# openSX70_ALADDIN_V395SEEED_20180208.net
KiCad netlist of a schematic drawn in EAGLE
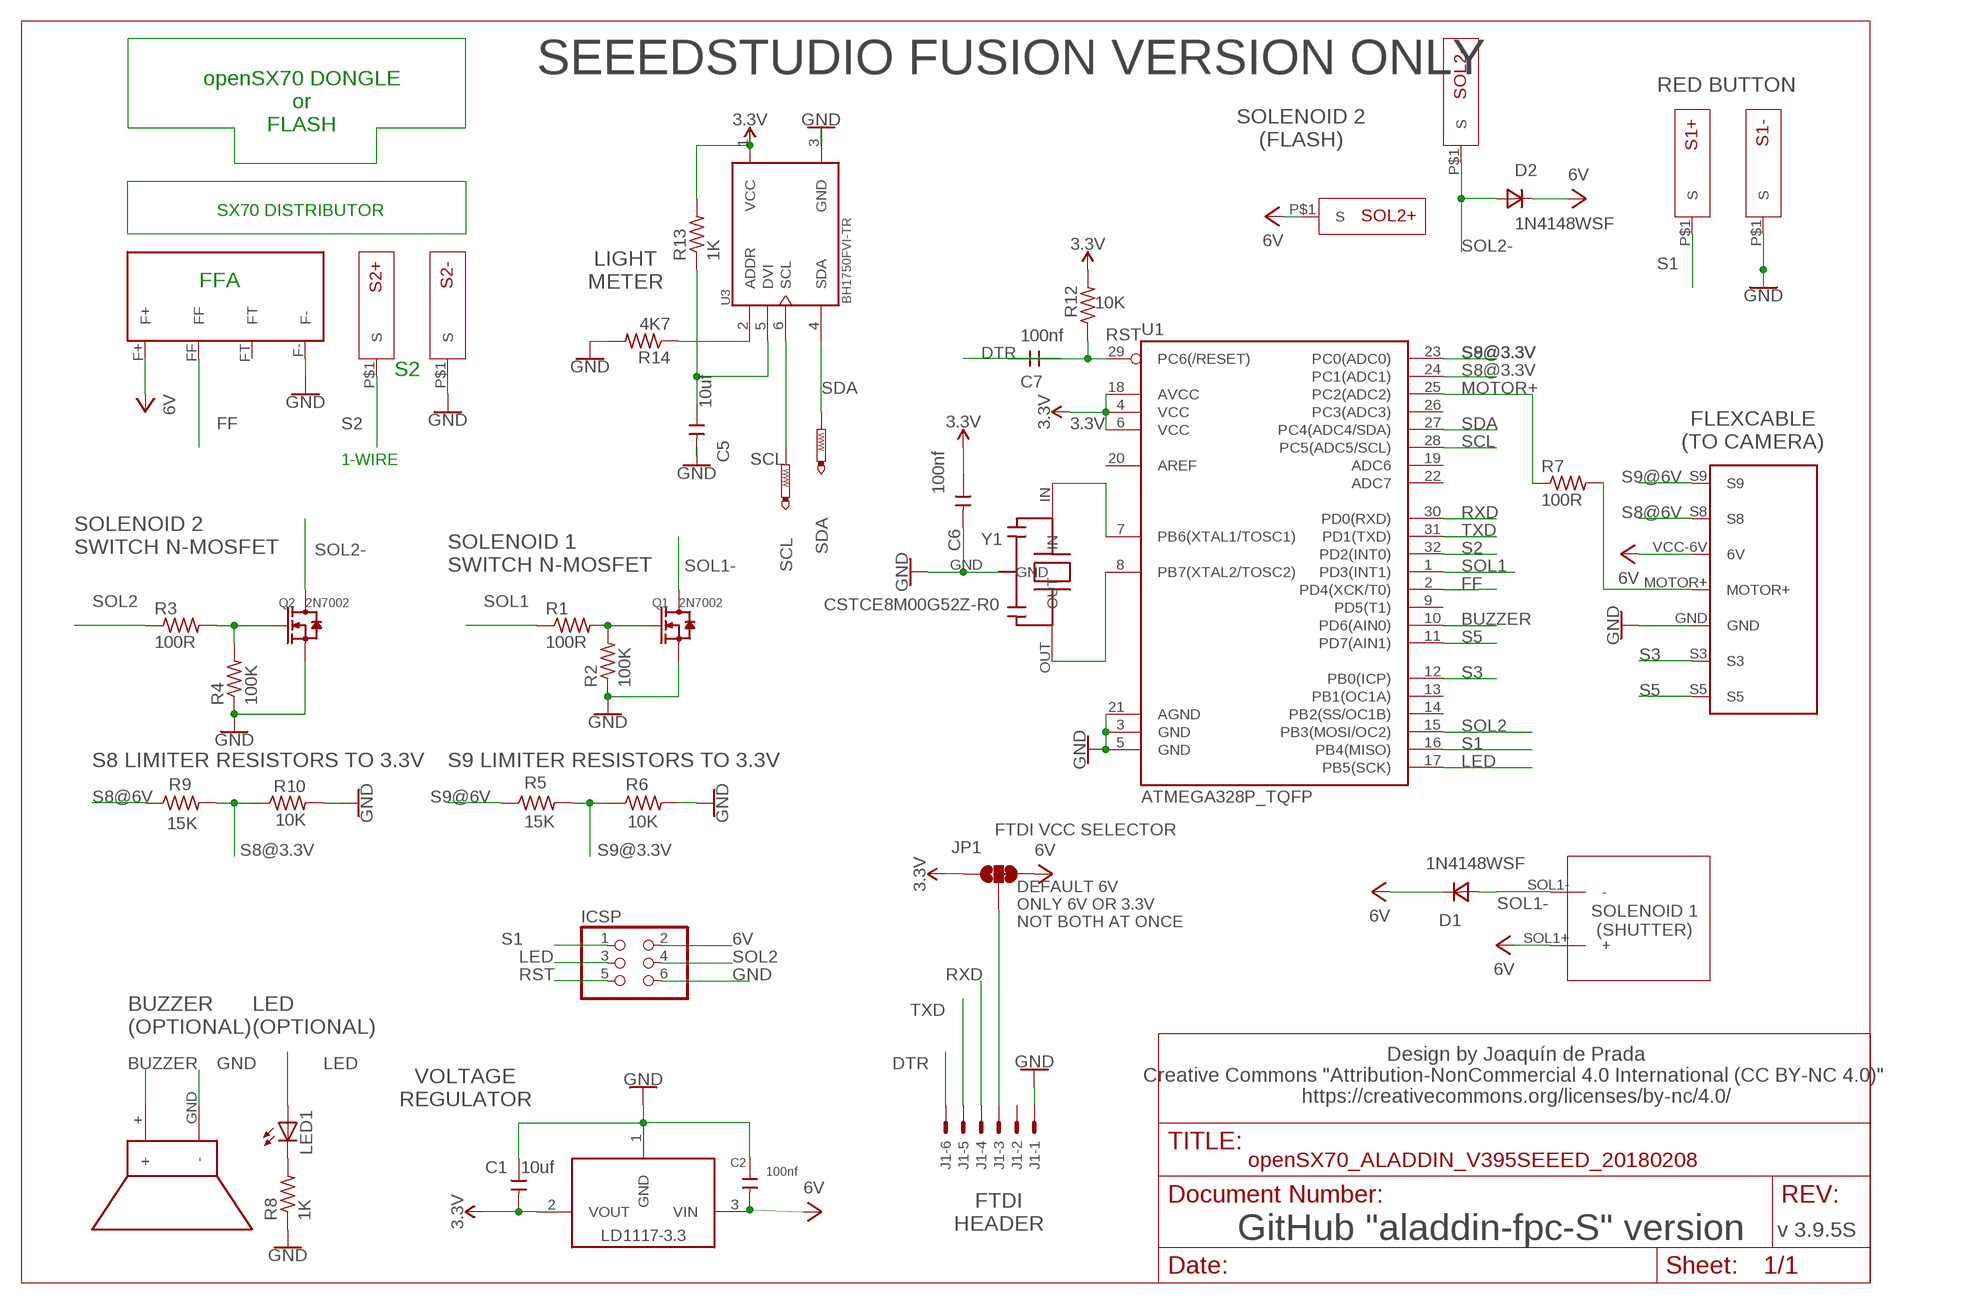
[diagram p0: schematic, sheet 1]

(export (version "E")
  (design (tool "Eeschema 10.0.6"))
  (components
    (comp (ref "C1")
      (value "10uf")
      (footprint "eagle-import:C0603")
      (fields (field (name "MPN") "CC0603KRX5R6BB106"))
      (libsource (lib "eagle-import") (part "CERAMIC-10UF-10V-10%-X5R(0603)"))
    )
    (comp (ref "C2")
      (value "100nf")
      (footprint "eagle-import:C0603")
      (fields (field (name "MPN") "CC0603KRX7R9BB104"))
      (libsource (lib "eagle-import") (part "CERAMIC-100NF-50V-10%-X7R(0603)"))
    )
    (comp (ref "C5")
      (value "10uf")
      (footprint "eagle-import:C0603")
      (fields (field (name "MPN") "CC0603KRX5R6BB106"))
      (libsource (lib "eagle-import") (part "CERAMIC-10UF-10V-10%-X5R(0603)"))
    )
    (comp (ref "C6")
      (value "100nf")
      (footprint "eagle-import:C0603")
      (fields (field (name "MPN") "CC0603KRX7R9BB104"))
      (libsource (lib "eagle-import") (part "CERAMIC-100NF-50V-10%-X7R(0603)"))
    )
    (comp (ref "C7")
      (value "100nf")
      (footprint "eagle-import:C0603")
      (fields (field (name "MPN") "CC0603KRX7R9BB104"))
      (libsource (lib "eagle-import") (part "CERAMIC-100NF-50V-10%-X7R(0603)"))
    )
    (comp (ref "D1")
      (value "1N4148WSF")
      (footprint "eagle-import:SOD323")
      (fields (field (name "MPN") "CDSOD323-T05C"))
      (libsource (lib "eagle-import") (part "DSOD323"))
    )
    (comp (ref "D2")
      (value "1N4148WSF")
      (footprint "eagle-import:SOD323")
      (fields (field (name "MPN") "CDSOD323-T05C"))
      (libsource (lib "eagle-import") (part "DSOD323"))
    )
    (comp (ref "ICSP")
      (value "PINHD-2X3")
      (footprint "eagle-import:2X03")
      (libsource (lib "eagle-import") (part "PINHD-2X3"))
    )
    (comp (ref "J1")
      (value "GND")
      (footprint "eagle-import:XF2L-0625-1")
      (fields (field (name "MF") "OMRON COMPONENTS USA") (field (name "MPN") "XF2L-0625-1"))
      (libsource (lib "eagle-import") (part "XF2-06?25-1L"))
    )
    (comp (ref "JP1")
      (value "FTDI VCC SELECTOR")
      (footprint "eagle-import:SMT-JUMPER_3_1-NC_TRACE_SILK")
      (libsource (lib "eagle-import") (part "JUMPER-SMT_3_1-NC_TRACE_SILK"))
    )
    (comp (ref "LD11172.5V")
      (value "LD1117 2.5V")
      (footprint "eagle-import:SOT223")
      (fields (field (name "MF") "Advanced Monolithic Systems") (field (name "MP") "AMS1117-5.0"))
      (libsource (lib "eagle-import") (part "LD1117-3.3"))
    )
    (comp (ref "LED1")
      (value "LEDCHIPLED_0805")
      (footprint "eagle-import:CHIPLED_0805")
      (libsource (lib "eagle-import") (part "LEDCHIPLED_0805"))
    )
    (comp (ref "Q1")
      (value "2N7002")
      (footprint "eagle-import:SOT-23")
      (fields (field (name "MPN") "2N7002,215"))
      (libsource (lib "eagle-import") (part "SMD-MOSFET-N-CH-60V-300MA-LOGIC-LEVEL-FET-2N7002(SOT-23)"))
    )
    (comp (ref "Q2")
      (value "2N7002")
      (footprint "eagle-import:SOT-23")
      (fields (field (name "MPN") "2N7002,215"))
      (libsource (lib "eagle-import") (part "SMD-MOSFET-N-CH-60V-300MA-LOGIC-LEVEL-FET-2N7002(SOT-23)"))
    )
    (comp (ref "R1")
      (value "100R")
      (footprint "eagle-import:R0603")
      (libsource (lib "eagle-import") (part "R-US_R0603"))
    )
    (comp (ref "R2")
      (value "100K")
      (footprint "eagle-import:R0603")
      (libsource (lib "eagle-import") (part "R-US_R0603"))
    )
    (comp (ref "R3")
      (value "100R")
      (footprint "eagle-import:R0603")
      (libsource (lib "eagle-import") (part "R-US_R0603"))
    )
    (comp (ref "R4")
      (value "100K")
      (footprint "eagle-import:R0603")
      (libsource (lib "eagle-import") (part "R-US_R0603"))
    )
    (comp (ref "R5")
      (value "15K")
      (footprint "eagle-import:R0603")
      (libsource (lib "eagle-import") (part "R-US_R0603"))
    )
    (comp (ref "R6")
      (value "10K")
      (footprint "eagle-import:R0603")
      (libsource (lib "eagle-import") (part "R-US_R0603"))
    )
    (comp (ref "R7")
      (value "100R")
      (footprint "eagle-import:R0603")
      (libsource (lib "eagle-import") (part "R-US_R0603"))
    )
    (comp (ref "R8")
      (value "1K")
      (footprint "eagle-import:R0603")
      (libsource (lib "eagle-import") (part "R-US_R0603"))
    )
    (comp (ref "R9")
      (value "15K")
      (footprint "eagle-import:R0603")
      (libsource (lib "eagle-import") (part "R-US_R0603"))
    )
    (comp (ref "R10")
      (value "10K")
      (footprint "eagle-import:R0603")
      (libsource (lib "eagle-import") (part "R-US_R0603"))
    )
    (comp (ref "R12")
      (value "10K")
      (footprint "eagle-import:R0603")
      (libsource (lib "eagle-import") (part "R-US_R0603"))
    )
    (comp (ref "R13")
      (value "1K")
      (footprint "eagle-import:R0603")
      (libsource (lib "eagle-import") (part "R-US_R0603"))
    )
    (comp (ref "R14")
      (value "4K7")
      (footprint "eagle-import:R0603")
      (libsource (lib "eagle-import") (part "R-US_R0603"))
    )
    (comp (ref "S1+")
      (value "SX70-S-PAD-NEW")
      (footprint "eagle-import:SX70-S-PAD2")
      (libsource (lib "eagle-import") (part "SX70-S-PAD-NEW"))
    )
    (comp (ref "S1-")
      (value "SX70-S-PAD-NEW")
      (footprint "eagle-import:SX70-S-PAD2")
      (libsource (lib "eagle-import") (part "SX70-S-PAD-NEW"))
    )
    (comp (ref "S2+")
      (value "SX70-S-PAD-NEW")
      (footprint "eagle-import:SX70-S-PAD2")
      (libsource (lib "eagle-import") (part "SX70-S-PAD-NEW"))
    )
    (comp (ref "S2-")
      (value "SX70-S-PAD-NEW")
      (footprint "eagle-import:SX70-S-PAD2")
      (libsource (lib "eagle-import") (part "SX70-S-PAD-NEW"))
    )
    (comp (ref "SCL")
      (value "PTR1TP08R")
      (footprint "eagle-import:TP08R")
      (libsource (lib "eagle-import") (part "PTR1TP08R"))
    )
    (comp (ref "SDA")
      (value "PTR1TP08R")
      (footprint "eagle-import:TP08R")
      (libsource (lib "eagle-import") (part "PTR1TP08R"))
    )
    (comp (ref "SOL1")
      (value "SX70-SOLENOID1-2PADS")
      (footprint "eagle-import:SX70-SOLENOID1-2")
      (libsource (lib "eagle-import") (part "SX70-SOLENOID1-2PADS"))
    )
    (comp (ref "SOL2+")
      (value "SX70-S-PAD-NEW")
      (footprint "eagle-import:SX70-S-PAD2")
      (libsource (lib "eagle-import") (part "SX70-S-PAD-NEW"))
    )
    (comp (ref "SOL2-")
      (value "SX70-S-PAD-NEW")
      (footprint "eagle-import:SX70-S-PAD2")
      (libsource (lib "eagle-import") (part "SX70-S-PAD-NEW"))
    )
    (comp (ref "U$1")
      (value "SX70-7-PAD")
      (footprint "eagle-import:SX70-7-PAD")
      (libsource (lib "eagle-import") (part "SX70-7-PAD"))
    )
    (comp (ref "U$2")
      (value "FFA")
      (footprint "eagle-import:FFA-PAD-PACKAGE")
      (libsource (lib "eagle-import") (part "SX70-FFA-PAD"))
    )
    (comp (ref "U$3")
      (value "CSET8-5G_V2")
      (footprint "eagle-import:CSET8-5G_PACKAGE")
      (libsource (lib "eagle-import") (part "CSET8-5G_V2"))
    )
    (comp (ref "U1")
      (value "ATMEGA328P_TQFP")
      (footprint "eagle-import:TQFP32-08")
      (libsource (lib "eagle-import") (part "ATMEGA328P_TQFP"))
    )
    (comp (ref "U3")
      (value "BH1750FVI-TR")
      (footprint "eagle-import:SOTFL50P300X75-6N")
      (fields (field (name "MF") "Rohm"))
      (libsource (lib "eagle-import") (part "BH1750FVI-TR"))
    )
    (comp (ref "Y1")
      (value "CSTCE8M00G52Z-R0")
      (footprint "eagle-import:CFP95P160X100-3N")
      (fields (field (name "MF") "Murata") (field (name "MP") "CSTCE16M0V53-R0"))
      (libsource (lib "eagle-import") (part "CSTCE16M0V53-R0"))
    )
  )
  (nets
    (net (code "1") (name "/BUZZER") (class "Default")
      (node (ref "U$3") (pin "+") (pinfunction "+_+") (pintype "bidirectional"))
      (node (ref "U1") (pin "10") (pinfunction "PD6(AIN0)_10") (pintype "bidirectional"))
    )
    (net (code "2") (name "/DTR") (class "Default")
      (node (ref "C7") (pin "1") (pinfunction "1_1") (pintype "passive"))
      (node (ref "J1") (pin "6") (pinfunction "MS_6") (pintype "passive"))
    )
    (net (code "3") (name "/FF") (class "Default")
      (node (ref "U$2") (pin "FF") (pinfunction "FF_FF") (pintype "bidirectional"))
      (node (ref "U1") (pin "2") (pinfunction "PD4(XCK/T0)_2") (pintype "bidirectional"))
    )
    (net (code "4") (name "/LED") (class "Default")
      (node (ref "ICSP") (pin "3") (pinfunction "3_3") (pintype "passive"))
      (node (ref "LED1") (pin "A") (pinfunction "A_A") (pintype "passive"))
      (node (ref "U1") (pin "17") (pinfunction "PB5(SCK)_17") (pintype "bidirectional"))
    )
    (net (code "5") (name "/MOTOR+") (class "Default")
      (node (ref "R7") (pin "1") (pinfunction "1_1") (pintype "passive"))
      (node (ref "U1") (pin "25") (pinfunction "PC2(ADC2)_25") (pintype "bidirectional"))
    )
    (net (code "6") (name "/RST") (class "Default")
      (node (ref "C7") (pin "2") (pinfunction "2_2") (pintype "passive"))
      (node (ref "ICSP") (pin "5") (pinfunction "5_5") (pintype "passive"))
      (node (ref "R12") (pin "1") (pinfunction "1_1") (pintype "passive"))
      (node (ref "U1") (pin "29") (pinfunction "PC6(/RESET)_29") (pintype "bidirectional"))
    )
    (net (code "7") (name "/RXD") (class "Default")
      (node (ref "J1") (pin "4") (pinfunction "MS_4") (pintype "passive"))
      (node (ref "U1") (pin "30") (pinfunction "PD0(RXD)_30") (pintype "bidirectional"))
    )
    (net (code "8") (name "/S1") (class "Default")
      (node (ref "ICSP") (pin "1") (pinfunction "1_1") (pintype "passive"))
      (node (ref "S1+") (pin "P$1") (pinfunction "S_P$1") (pintype "bidirectional"))
      (node (ref "U1") (pin "16") (pinfunction "PB4(MISO)_16") (pintype "bidirectional"))
    )
    (net (code "9") (name "/S2") (class "Default")
      (node (ref "S2+") (pin "P$1") (pinfunction "S_P$1") (pintype "bidirectional"))
      (node (ref "U1") (pin "32") (pinfunction "PD2(INT0)_32") (pintype "bidirectional"))
    )
    (net (code "10") (name "/S3") (class "Default")
      (node (ref "U$1") (pin "S3") (pinfunction "S3_S3") (pintype "bidirectional"))
      (node (ref "U1") (pin "12") (pinfunction "PB0(ICP)_12") (pintype "bidirectional"))
    )
    (net (code "11") (name "/S5") (class "Default")
      (node (ref "U$1") (pin "S5") (pinfunction "S5_S5") (pintype "bidirectional"))
      (node (ref "U1") (pin "11") (pinfunction "PD7(AIN1)_11") (pintype "bidirectional"))
    )
    (net (code "12") (name "/S8@3.3V") (class "Default")
      (node (ref "R10") (pin "1") (pinfunction "1_1") (pintype "passive"))
      (node (ref "R9") (pin "2") (pinfunction "2_2") (pintype "passive"))
      (node (ref "U1") (pin "24") (pinfunction "PC1(ADC1)_24") (pintype "bidirectional"))
    )
    (net (code "13") (name "/S8@6V") (class "Default")
      (node (ref "R9") (pin "1") (pinfunction "1_1") (pintype "passive"))
      (node (ref "U$1") (pin "S8") (pinfunction "S8_S8") (pintype "bidirectional"))
    )
    (net (code "14") (name "/S9@3.3V") (class "Default")
      (node (ref "R5") (pin "2") (pinfunction "2_2") (pintype "passive"))
      (node (ref "R6") (pin "1") (pinfunction "1_1") (pintype "passive"))
      (node (ref "U1") (pin "23") (pinfunction "PC0(ADC0)_23") (pintype "bidirectional"))
    )
    (net (code "15") (name "/S9@6V") (class "Default")
      (node (ref "R5") (pin "1") (pinfunction "1_1") (pintype "passive"))
      (node (ref "U$1") (pin "S9") (pinfunction "S9_S9") (pintype "bidirectional"))
    )
    (net (code "16") (name "/SCL") (class "Default")
      (node (ref "SCL") (pin "TP") (pinfunction "TP_TP") (pintype "input"))
      (node (ref "U1") (pin "28") (pinfunction "PC5(ADC5/SCL)_28") (pintype "bidirectional"))
      (node (ref "U3") (pin "6") (pinfunction "SCL_6") (pintype "input"))
    )
    (net (code "17") (name "/SDA") (class "Default")
      (node (ref "SDA") (pin "TP") (pinfunction "TP_TP") (pintype "input"))
      (node (ref "U1") (pin "27") (pinfunction "PC4(ADC4/SDA)_27") (pintype "bidirectional"))
      (node (ref "U3") (pin "4") (pinfunction "SDA_4") (pintype "bidirectional"))
    )
    (net (code "18") (name "/SOL1") (class "Default")
      (node (ref "R1") (pin "1") (pinfunction "1_1") (pintype "passive"))
      (node (ref "U1") (pin "1") (pinfunction "PD3(INT1)_1") (pintype "bidirectional"))
    )
    (net (code "19") (name "/SOL1-") (class "Default")
      (node (ref "D1") (pin "2") (pinfunction "A_2") (pintype "passive"))
      (node (ref "Q1") (pin "3") (pinfunction "D_3") (pintype "passive"))
      (node (ref "SOL1") (pin "SOL1-") (pinfunction "-_SOL1-") (pintype "bidirectional"))
    )
    (net (code "20") (name "/SOL2") (class "Default")
      (node (ref "ICSP") (pin "4") (pinfunction "4_4") (pintype "passive"))
      (node (ref "R3") (pin "1") (pinfunction "1_1") (pintype "passive"))
      (node (ref "U1") (pin "15") (pinfunction "PB3(MOSI/OC2)_15") (pintype "bidirectional"))
    )
    (net (code "21") (name "/SOL2-") (class "Default")
      (node (ref "D2") (pin "2") (pinfunction "A_2") (pintype "passive"))
      (node (ref "Q2") (pin "3") (pinfunction "D_3") (pintype "passive"))
      (node (ref "SOL2-") (pin "P$1") (pinfunction "S_P$1") (pintype "bidirectional"))
    )
    (net (code "22") (name "/TXD") (class "Default")
      (node (ref "J1") (pin "5") (pinfunction "MS_5") (pintype "passive"))
      (node (ref "U1") (pin "31") (pinfunction "PD1(TXD)_31") (pintype "bidirectional"))
    )
    (net (code "23") (name "3.3V") (class "Default")
      (node (ref "C1") (pin "2") (pinfunction "2_2") (pintype "passive"))
      (node (ref "C6") (pin "1") (pinfunction "1_1") (pintype "passive"))
      (node (ref "JP1") (pin "1") (pinfunction "1_1") (pintype "passive"))
      (node (ref "LD11172.5V") (pin "2") (pinfunction "VOUT_2") (pintype "bidirectional"))
      (node (ref "R12") (pin "2") (pinfunction "2_2") (pintype "passive"))
      (node (ref "R13") (pin "2") (pinfunction "2_2") (pintype "passive"))
      (node (ref "U1") (pin "18") (pinfunction "AVCC_18") (pintype "bidirectional"))
      (node (ref "U1") (pin "4") (pinfunction "VCC_4") (pintype "bidirectional"))
      (node (ref "U1") (pin "6") (pinfunction "VCC_6") (pintype "bidirectional"))
      (node (ref "U3") (pin "1") (pinfunction "VCC_1") (pintype "power_in"))
    )
    (net (code "24") (name "6V") (class "Default")
      (node (ref "C2") (pin "2") (pinfunction "2_2") (pintype "passive"))
      (node (ref "D1") (pin "1") (pinfunction "C_1") (pintype "passive"))
      (node (ref "D2") (pin "1") (pinfunction "C_1") (pintype "passive"))
      (node (ref "ICSP") (pin "2") (pinfunction "2_2") (pintype "passive"))
      (node (ref "JP1") (pin "3") (pinfunction "3_3") (pintype "passive"))
      (node (ref "LD11172.5V") (pin "3") (pinfunction "VIN_3") (pintype "bidirectional"))
      (node (ref "SOL1") (pin "SOL1+") (pinfunction "+_SOL1+") (pintype "bidirectional"))
      (node (ref "SOL2+") (pin "P$1") (pinfunction "S_P$1") (pintype "bidirectional"))
      (node (ref "U$1") (pin "VCC-6V") (pinfunction "6V_VCC-6V") (pintype "bidirectional"))
      (node (ref "U$2") (pin "F+") (pinfunction "F+_F+") (pintype "bidirectional"))
    )
    (net (code "25") (name "GND") (class "Default")
      (node (ref "C1") (pin "1") (pinfunction "1_1") (pintype "passive"))
      (node (ref "C2") (pin "1") (pinfunction "1_1") (pintype "passive"))
      (node (ref "C5") (pin "2") (pinfunction "2_2") (pintype "passive"))
      (node (ref "C6") (pin "2") (pinfunction "2_2") (pintype "passive"))
      (node (ref "ICSP") (pin "6") (pinfunction "6_6") (pintype "passive"))
      (node (ref "J1") (pin "1") (pinfunction "MS_1") (pintype "passive"))
      (node (ref "LD11172.5V") (pin "1") (pinfunction "GND_1") (pintype "bidirectional"))
      (node (ref "Q1") (pin "2") (pinfunction "S_2") (pintype "passive"))
      (node (ref "Q2") (pin "2") (pinfunction "S_2") (pintype "passive"))
      (node (ref "R10") (pin "2") (pinfunction "2_2") (pintype "passive"))
      (node (ref "R14") (pin "2") (pinfunction "2_2") (pintype "passive"))
      (node (ref "R2") (pin "1") (pinfunction "1_1") (pintype "passive"))
      (node (ref "R4") (pin "1") (pinfunction "1_1") (pintype "passive"))
      (node (ref "R6") (pin "2") (pinfunction "2_2") (pintype "passive"))
      (node (ref "R8") (pin "1") (pinfunction "1_1") (pintype "passive"))
      (node (ref "S1-") (pin "P$1") (pinfunction "S_P$1") (pintype "bidirectional"))
      (node (ref "S2-") (pin "P$1") (pinfunction "S_P$1") (pintype "bidirectional"))
      (node (ref "U$1") (pin "GND") (pinfunction "GND_GND") (pintype "bidirectional"))
      (node (ref "U$2") (pin "F-") (pinfunction "F-_F-") (pintype "bidirectional"))
      (node (ref "U$3") (pin "GND") (pinfunction "-_GND") (pintype "bidirectional"))
      (node (ref "U1") (pin "21") (pinfunction "AGND_21") (pintype "bidirectional"))
      (node (ref "U1") (pin "3") (pinfunction "GND_3") (pintype "bidirectional"))
      (node (ref "U1") (pin "5") (pinfunction "GND_5") (pintype "bidirectional"))
      (node (ref "U3") (pin "3") (pinfunction "GND_3") (pintype "power_in"))
      (node (ref "Y1") (pin "GND") (pinfunction "GND_GND") (pintype "passive"))
    )
    (net (code "26") (name "Net-(J1C-MS)") (class "Default")
      (node (ref "J1") (pin "3") (pinfunction "MS_3") (pintype "passive"))
      (node (ref "JP1") (pin "2") (pinfunction "2_2") (pintype "passive"))
    )
    (net (code "27") (name "Net-(LED1-PadC)") (class "Default")
      (node (ref "LED1") (pin "C") (pinfunction "C_C") (pintype "passive"))
      (node (ref "R8") (pin "2") (pinfunction "2_2") (pintype "passive"))
    )
    (net (code "28") (name "Net-(Q1-G)") (class "Default")
      (node (ref "Q1") (pin "1") (pinfunction "G_1") (pintype "passive"))
      (node (ref "R1") (pin "2") (pinfunction "2_2") (pintype "passive"))
      (node (ref "R2") (pin "2") (pinfunction "2_2") (pintype "passive"))
    )
    (net (code "29") (name "Net-(Q2-G)") (class "Default")
      (node (ref "Q2") (pin "1") (pinfunction "G_1") (pintype "passive"))
      (node (ref "R3") (pin "2") (pinfunction "2_2") (pintype "passive"))
      (node (ref "R4") (pin "2") (pinfunction "2_2") (pintype "passive"))
    )
    (net (code "30") (name "Net-(R7-Pad2)") (class "Default")
      (node (ref "R7") (pin "2") (pinfunction "2_2") (pintype "passive"))
      (node (ref "U$1") (pin "MOTOR+") (pinfunction "MOTOR+_MOTOR+") (pintype "bidirectional"))
    )
    (net (code "31") (name "Net-(U1-PB6(XTAL1{slash}TOSC1))") (class "Default")
      (node (ref "U1") (pin "7") (pinfunction "PB6(XTAL1/TOSC1)_7") (pintype "bidirectional"))
      (node (ref "Y1") (pin "IN") (pinfunction "IN_IN") (pintype "input"))
    )
    (net (code "32") (name "Net-(U1-PB7(XTAL2{slash}TOSC2))") (class "Default")
      (node (ref "U1") (pin "8") (pinfunction "PB7(XTAL2/TOSC2)_8") (pintype "bidirectional"))
      (node (ref "Y1") (pin "OUT") (pinfunction "OUT_OUT") (pintype "output"))
    )
    (net (code "33") (name "Net-(U3-ADDR)") (class "Default")
      (node (ref "R14") (pin "1") (pinfunction "1_1") (pintype "passive"))
      (node (ref "U3") (pin "2") (pinfunction "ADDR_2") (pintype "input"))
    )
    (net (code "34") (name "Net-(U3-DVI)") (class "Default")
      (node (ref "C5") (pin "1") (pinfunction "1_1") (pintype "passive"))
      (node (ref "R13") (pin "1") (pinfunction "1_1") (pintype "passive"))
      (node (ref "U3") (pin "5") (pinfunction "DVI_5") (pintype "input"))
    )
    (net (code "35") (name "unconnected-(J1B-MS-Pad2)") (class "Default")
      (node (ref "J1") (pin "2") (pinfunction "MS_2") (pintype "passive"))
    )
    (net (code "36") (name "unconnected-(U$2-PadFT)") (class "Default")
      (node (ref "U$2") (pin "FT") (pinfunction "FT_FT") (pintype "bidirectional"))
    )
    (net (code "37") (name "unconnected-(U1-ADC6-Pad19)") (class "Default")
      (node (ref "U1") (pin "19") (pinfunction "ADC6_19") (pintype "bidirectional"))
    )
    (net (code "38") (name "unconnected-(U1-ADC7-Pad22)") (class "Default")
      (node (ref "U1") (pin "22") (pinfunction "ADC7_22") (pintype "bidirectional"))
    )
    (net (code "39") (name "unconnected-(U1-AREF-Pad20)") (class "Default")
      (node (ref "U1") (pin "20") (pinfunction "AREF_20") (pintype "bidirectional"))
    )
    (net (code "40") (name "unconnected-(U1-PB1(OC1A)-Pad13)") (class "Default")
      (node (ref "U1") (pin "13") (pinfunction "PB1(OC1A)_13") (pintype "bidirectional"))
    )
    (net (code "41") (name "unconnected-(U1-PB2(SS{slash}OC1B)-Pad14)") (class "Default")
      (node (ref "U1") (pin "14") (pinfunction "PB2(SS/OC1B)_14") (pintype "bidirectional"))
    )
    (net (code "42") (name "unconnected-(U1-PC3(ADC3)-Pad26)") (class "Default")
      (node (ref "U1") (pin "26") (pinfunction "PC3(ADC3)_26") (pintype "bidirectional"))
    )
    (net (code "43") (name "unconnected-(U1-PD5(T1)-Pad9)") (class "Default")
      (node (ref "U1") (pin "9") (pinfunction "PD5(T1)_9") (pintype "bidirectional"))
    )
  )
)
